# Underwater_Camera_Rev_A.net
KiCad netlist of a schematic drawn in EAGLE
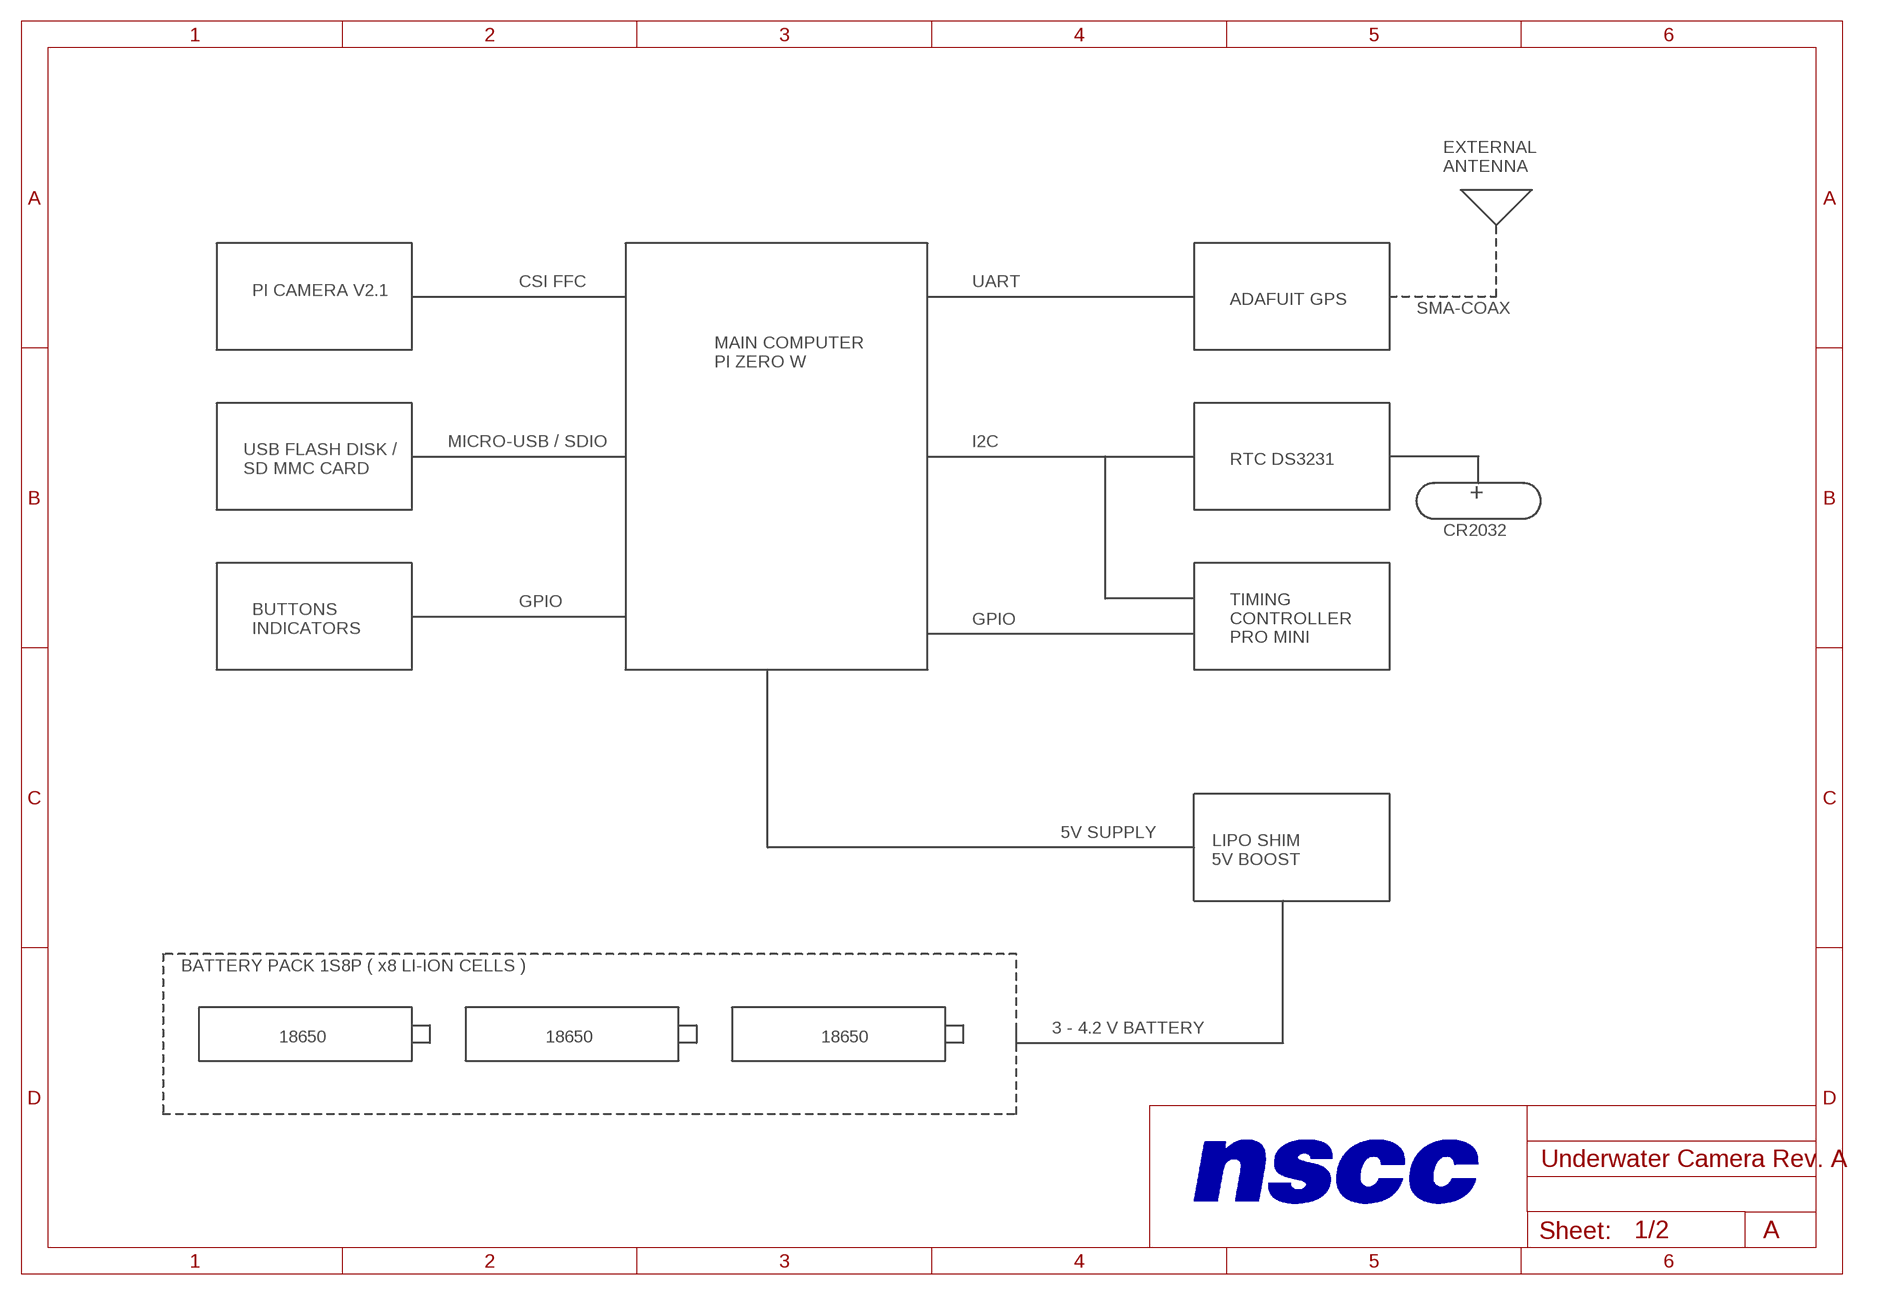
[diagram p0: schematic, sheet 1]
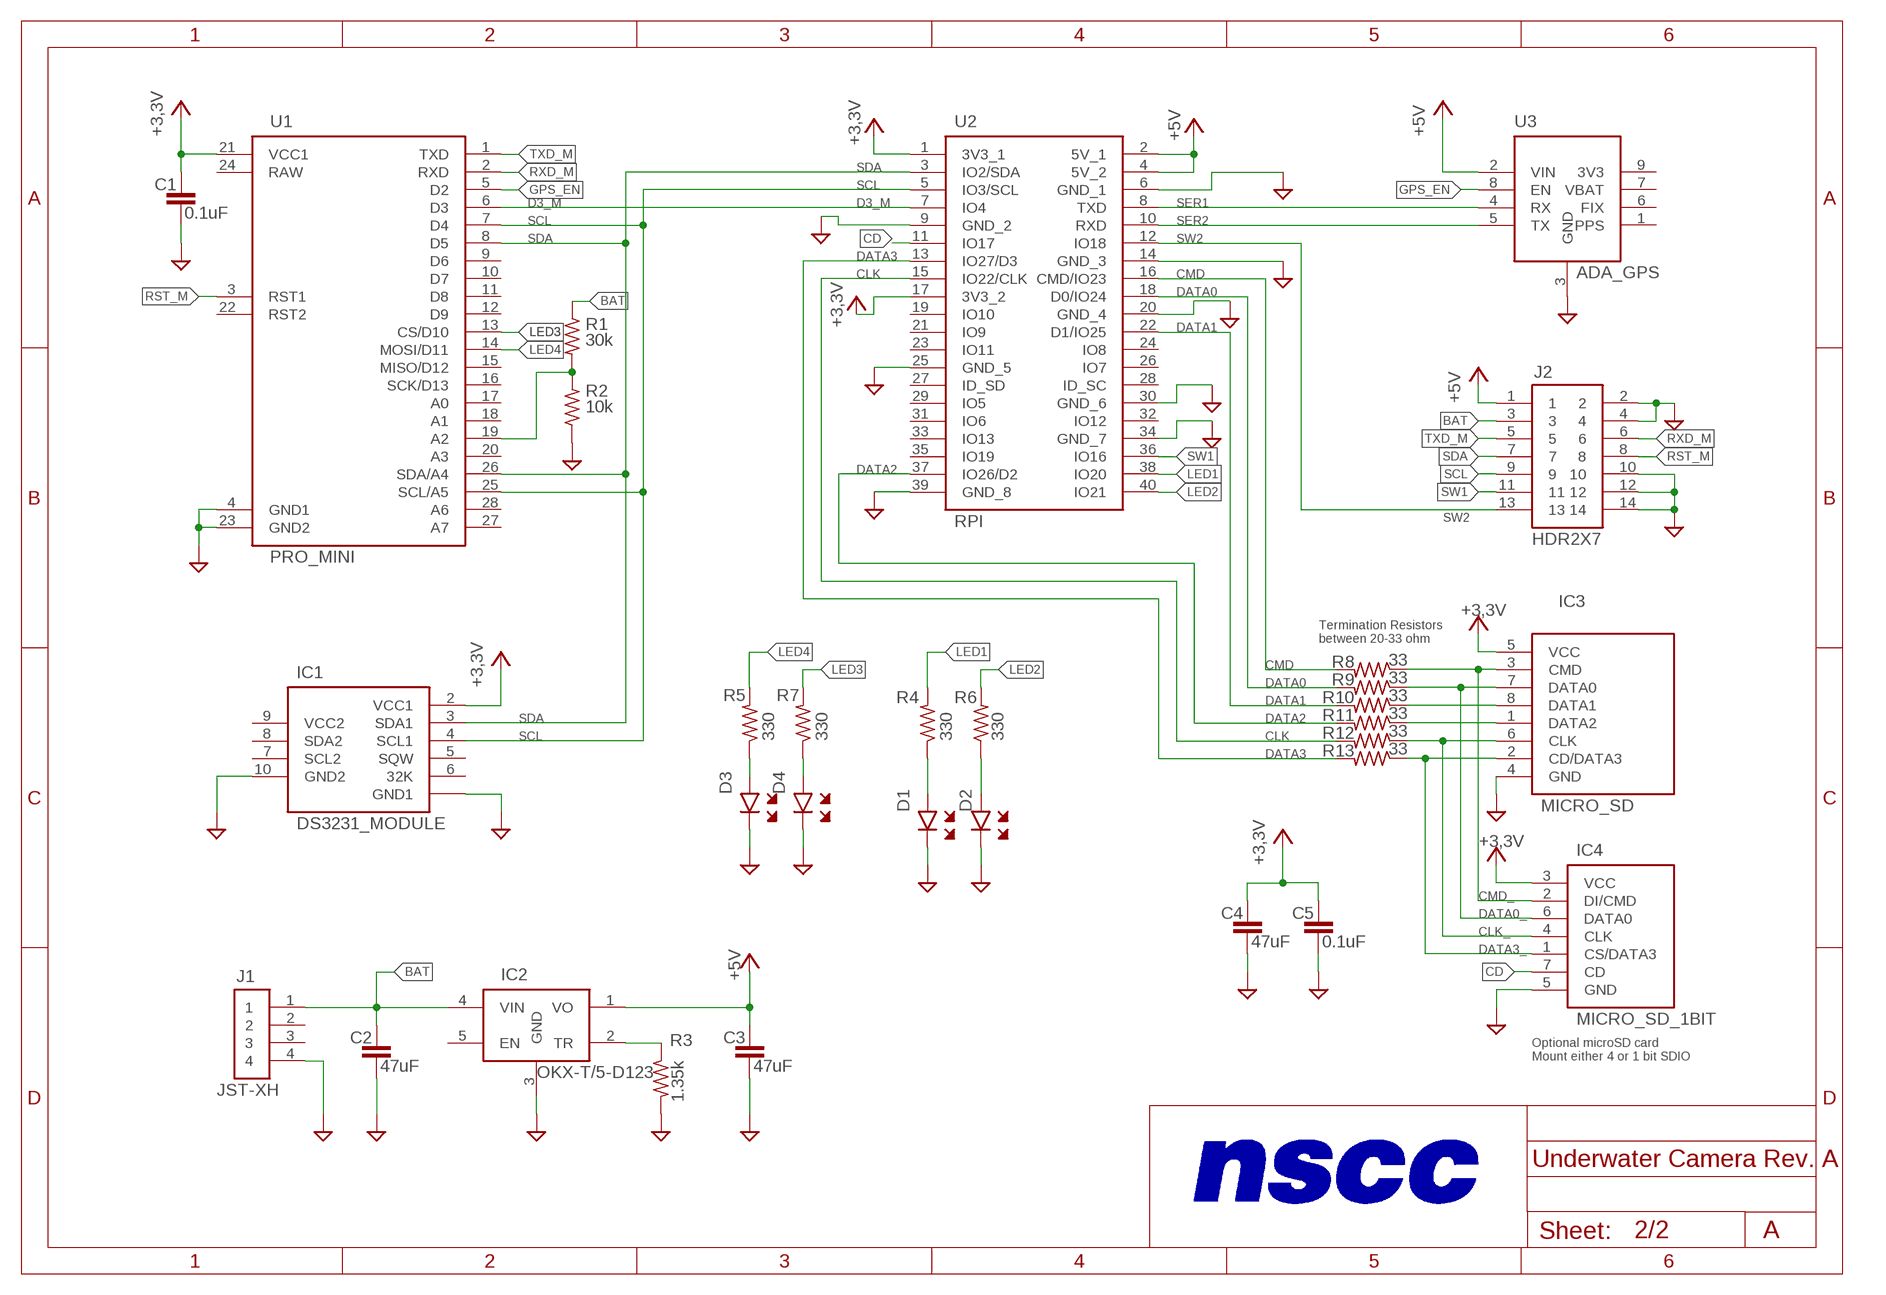
[diagram p1: schematic, sheet 2]

(export (version "E")
  (design (tool "Eeschema 10.0.6"))
  (components
    (comp (ref "C1")
      (value "0.1uF")
      (footprint "eagle-import:CAPPRD254W65D300H300B")
      (libsource (lib "eagle-import") (part "CAP_THCAP-TH-2MM"))
    )
    (comp (ref "C2")
      (value "47uF")
      (footprint "eagle-import:CAPPRD508W65D1000H1100B")
      (libsource (lib "eagle-import") (part "CAP_THCAP-ELECTRO-5.08"))
    )
    (comp (ref "C3")
      (value "47uF")
      (footprint "eagle-import:CAPPRD508W65D1000H1100B")
      (libsource (lib "eagle-import") (part "CAP_THCAP-ELECTRO-5.08"))
    )
    (comp (ref "C4")
      (value "47uF")
      (footprint "eagle-import:CAPPRD508W65D1000H1100B")
      (libsource (lib "eagle-import") (part "CAP_THCAP-ELECTRO-5.08"))
    )
    (comp (ref "C5")
      (value "0.1uF")
      (footprint "eagle-import:CAPPRD254W65D300H300B")
      (libsource (lib "eagle-import") (part "CAP_THCAP-TH-2MM"))
    )
    (comp (ref "D1")
      (value "LED_THLED-2.54")
      (footprint "eagle-import:LEDRD254W60D565H860B")
      (libsource (lib "eagle-import") (part "LED_THLED-2.54"))
    )
    (comp (ref "D2")
      (value "LED_THLED-2.54")
      (footprint "eagle-import:LEDRD254W60D565H860B")
      (libsource (lib "eagle-import") (part "LED_THLED-2.54"))
    )
    (comp (ref "D3")
      (value "LED_THLED-2.54")
      (footprint "eagle-import:LEDRD254W60D565H860B")
      (libsource (lib "eagle-import") (part "LED_THLED-2.54"))
    )
    (comp (ref "D4")
      (value "LED_THLED-2.54")
      (footprint "eagle-import:LEDRD254W60D565H860B")
      (libsource (lib "eagle-import") (part "LED_THLED-2.54"))
    )
    (comp (ref "IC1")
      (value "DS3231_MODULE")
      (footprint "eagle-import:DS3231_MODULE")
      (libsource (lib "eagle-import") (part "DS3231_MODULE"))
    )
    (comp (ref "IC2")
      (value "OKX-T/5-D123")
      (footprint "eagle-import:OKX-T_5-D12")
      (libsource (lib "eagle-import") (part "OKX-T/5-D123DMODEL"))
    )
    (comp (ref "IC3")
      (value "MICRO_SD")
      (footprint "eagle-import:MICRO_SD_SDIO")
      (libsource (lib "eagle-import") (part "MICRO_SD_SNIFFER"))
    )
    (comp (ref "IC4")
      (value "MICRO_SD_1BIT")
      (footprint "eagle-import:MICRO_SD_SDIO1B")
      (libsource (lib "eagle-import") (part "MICRO_SD"))
    )
    (comp (ref "J1")
      (value "JST-XH")
      (footprint "eagle-import:HDR1X4")
      (libsource (lib "eagle-import") (part "HDR1X4JST-XH"))
    )
    (comp (ref "J2")
      (value "HDR2X7")
      (footprint "eagle-import:HDR2X7")
      (libsource (lib "eagle-import") (part "HDR2X7HDR2X7"))
    )
    (comp (ref "R1")
      (value "30k")
      (footprint "eagle-import:RESAD1176W63L850D250B")
      (libsource (lib "eagle-import") (part "RES_THRES-D8.5"))
    )
    (comp (ref "R2")
      (value "10k")
      (footprint "eagle-import:RESAD1176W63L850D250B")
      (libsource (lib "eagle-import") (part "RES_THRES-D8.5"))
    )
    (comp (ref "R3")
      (value "1.35k")
      (footprint "eagle-import:RESAD1176W63L850D250B")
      (libsource (lib "eagle-import") (part "RES_THRES-D8.5"))
    )
    (comp (ref "R4")
      (value "330")
      (footprint "eagle-import:RESAD1176W63L850D250B")
      (libsource (lib "eagle-import") (part "RES_THRES-D8.5"))
    )
    (comp (ref "R5")
      (value "330")
      (footprint "eagle-import:RESAD1176W63L850D250B")
      (libsource (lib "eagle-import") (part "RES_THRES-D8.5"))
    )
    (comp (ref "R6")
      (value "330")
      (footprint "eagle-import:RESAD1176W63L850D250B")
      (libsource (lib "eagle-import") (part "RES_THRES-D8.5"))
    )
    (comp (ref "R7")
      (value "330")
      (footprint "eagle-import:RESAD1176W63L850D250B")
      (libsource (lib "eagle-import") (part "RES_THRES-D8.5"))
    )
    (comp (ref "R8")
      (value "33")
      (footprint "eagle-import:RESAD1176W63L850D250B")
      (libsource (lib "eagle-import") (part "RES_THRES-D8.5"))
    )
    (comp (ref "R9")
      (value "33")
      (footprint "eagle-import:RESAD1176W63L850D250B")
      (libsource (lib "eagle-import") (part "RES_THRES-D8.5"))
    )
    (comp (ref "R10")
      (value "33")
      (footprint "eagle-import:RESAD1176W63L850D250B")
      (libsource (lib "eagle-import") (part "RES_THRES-D8.5"))
    )
    (comp (ref "R11")
      (value "33")
      (footprint "eagle-import:RESAD1176W63L850D250B")
      (libsource (lib "eagle-import") (part "RES_THRES-D8.5"))
    )
    (comp (ref "R12")
      (value "33")
      (footprint "eagle-import:RESAD1176W63L850D250B")
      (libsource (lib "eagle-import") (part "RES_THRES-D8.5"))
    )
    (comp (ref "R13")
      (value "33")
      (footprint "eagle-import:RESAD1176W63L850D250B")
      (libsource (lib "eagle-import") (part "RES_THRES-D8.5"))
    )
    (comp (ref "U1")
      (value "PRO_MINI")
      (footprint "eagle-import:PRO_MINI")
      (libsource (lib "eagle-import") (part "PRO_MINI"))
    )
    (comp (ref "U2")
      (value "RPI")
      (footprint "eagle-import:PI_ZERO_W")
      (libsource (lib "eagle-import") (part "RPI"))
    )
    (comp (ref "U3")
      (value "ADA_GPS")
      (footprint "eagle-import:ADA_ULTIMATE_GPS")
      (libsource (lib "eagle-import") (part "ADA_ULTIMATE_GPS9P_BREAKOUT"))
    )
  )
  (nets
    (net (code "1") (name "+3,3V") (class "Default")
      (node (ref "C1") (pin "1") (pinfunction "1_1") (pintype "passive"))
      (node (ref "C4") (pin "1") (pinfunction "1_1") (pintype "passive"))
      (node (ref "C5") (pin "1") (pinfunction "1_1") (pintype "passive"))
      (node (ref "IC1") (pin "2") (pinfunction "VCC1_2") (pintype "bidirectional"))
      (node (ref "IC3") (pin "5") (pinfunction "VCC_5") (pintype "bidirectional"))
      (node (ref "IC4") (pin "3") (pinfunction "VCC_3") (pintype "bidirectional"))
      (node (ref "U1") (pin "21") (pinfunction "VCC1_21") (pintype "bidirectional"))
      (node (ref "U2") (pin "1") (pinfunction "3V3_1_1") (pintype "bidirectional"))
      (node (ref "U2") (pin "17") (pinfunction "3V3_2_17") (pintype "bidirectional"))
    )
    (net (code "2") (name "+5V") (class "Default")
      (node (ref "C3") (pin "1") (pinfunction "1_1") (pintype "passive"))
      (node (ref "IC2") (pin "1") (pinfunction "VO_1") (pintype "bidirectional"))
      (node (ref "J2") (pin "1") (pinfunction "1_1") (pintype "bidirectional"))
      (node (ref "U2") (pin "2") (pinfunction "5V_1_2") (pintype "bidirectional"))
      (node (ref "U2") (pin "4") (pinfunction "5V_2_4") (pintype "bidirectional"))
      (node (ref "U3") (pin "2") (pinfunction "VIN_2") (pintype "bidirectional"))
    )
    (net (code "3") (name "BAT") (class "Default")
      (node (ref "C2") (pin "1") (pinfunction "1_1") (pintype "passive"))
      (node (ref "IC2") (pin "4") (pinfunction "VIN_4") (pintype "bidirectional"))
      (node (ref "J1") (pin "1") (pinfunction "1_1") (pintype "bidirectional"))
      (node (ref "J2") (pin "3") (pinfunction "3_3") (pintype "bidirectional"))
      (node (ref "R1") (pin "1") (pinfunction "1_1") (pintype "passive"))
    )
    (net (code "4") (name "CD") (class "Default")
      (node (ref "IC4") (pin "7") (pinfunction "CD_7") (pintype "bidirectional"))
      (node (ref "U2") (pin "11") (pinfunction "IO17_11") (pintype "bidirectional"))
    )
    (net (code "5") (name "CLK") (class "Default")
      (node (ref "R12") (pin "2") (pinfunction "2_2") (pintype "passive"))
      (node (ref "U2") (pin "15") (pinfunction "IO22/CLK_15") (pintype "bidirectional"))
    )
    (net (code "6") (name "CLK_") (class "Default")
      (node (ref "IC3") (pin "6") (pinfunction "CLK_6") (pintype "bidirectional"))
      (node (ref "IC4") (pin "4") (pinfunction "CLK_4") (pintype "bidirectional"))
      (node (ref "R12") (pin "1") (pinfunction "1_1") (pintype "passive"))
    )
    (net (code "7") (name "CMD") (class "Default")
      (node (ref "R8") (pin "2") (pinfunction "2_2") (pintype "passive"))
      (node (ref "U2") (pin "16") (pinfunction "CMD/IO23_16") (pintype "bidirectional"))
    )
    (net (code "8") (name "CMD_") (class "Default")
      (node (ref "IC3") (pin "3") (pinfunction "CMD_3") (pintype "bidirectional"))
      (node (ref "IC4") (pin "2") (pinfunction "DI/CMD_2") (pintype "bidirectional"))
      (node (ref "R8") (pin "1") (pinfunction "1_1") (pintype "passive"))
    )
    (net (code "9") (name "D3_M") (class "Default")
      (node (ref "U1") (pin "6") (pinfunction "D3_6") (pintype "bidirectional"))
      (node (ref "U2") (pin "7") (pinfunction "IO4_7") (pintype "bidirectional"))
    )
    (net (code "10") (name "DATA0") (class "Default")
      (node (ref "R9") (pin "2") (pinfunction "2_2") (pintype "passive"))
      (node (ref "U2") (pin "18") (pinfunction "D0/IO24_18") (pintype "bidirectional"))
    )
    (net (code "11") (name "DATA0_") (class "Default")
      (node (ref "IC3") (pin "7") (pinfunction "DATA0_7") (pintype "bidirectional"))
      (node (ref "IC4") (pin "6") (pinfunction "DATA0_6") (pintype "bidirectional"))
      (node (ref "R9") (pin "1") (pinfunction "1_1") (pintype "passive"))
    )
    (net (code "12") (name "DATA1") (class "Default")
      (node (ref "R10") (pin "2") (pinfunction "2_2") (pintype "passive"))
      (node (ref "U2") (pin "22") (pinfunction "D1/IO25_22") (pintype "bidirectional"))
    )
    (net (code "13") (name "DATA2") (class "Default")
      (node (ref "R11") (pin "2") (pinfunction "2_2") (pintype "passive"))
      (node (ref "U2") (pin "37") (pinfunction "IO26/D2_37") (pintype "bidirectional"))
    )
    (net (code "14") (name "DATA3") (class "Default")
      (node (ref "R13") (pin "2") (pinfunction "2_2") (pintype "passive"))
      (node (ref "U2") (pin "13") (pinfunction "IO27/D3_13") (pintype "bidirectional"))
    )
    (net (code "15") (name "DATA3_") (class "Default")
      (node (ref "IC3") (pin "2") (pinfunction "CD/DATA3_2") (pintype "bidirectional"))
      (node (ref "IC4") (pin "1") (pinfunction "CS/DATA3_1") (pintype "bidirectional"))
      (node (ref "R13") (pin "1") (pinfunction "1_1") (pintype "passive"))
    )
    (net (code "16") (name "GND") (class "Default")
      (node (ref "C1") (pin "2") (pinfunction "2_2") (pintype "passive"))
      (node (ref "C2") (pin "2") (pinfunction "2_2") (pintype "passive"))
      (node (ref "C3") (pin "2") (pinfunction "2_2") (pintype "passive"))
      (node (ref "C4") (pin "2") (pinfunction "2_2") (pintype "passive"))
      (node (ref "C5") (pin "2") (pinfunction "2_2") (pintype "passive"))
      (node (ref "D1") (pin "2") (pinfunction "P$2_2") (pintype "bidirectional"))
      (node (ref "D2") (pin "2") (pinfunction "P$2_2") (pintype "bidirectional"))
      (node (ref "D3") (pin "2") (pinfunction "P$2_2") (pintype "bidirectional"))
      (node (ref "D4") (pin "2") (pinfunction "P$2_2") (pintype "bidirectional"))
      (node (ref "IC1") (pin "1") (pinfunction "GND1_1") (pintype "bidirectional"))
      (node (ref "IC1") (pin "10") (pinfunction "GND2_10") (pintype "bidirectional"))
      (node (ref "IC2") (pin "3") (pinfunction "GND_3") (pintype "bidirectional"))
      (node (ref "IC3") (pin "4") (pinfunction "GND_4") (pintype "bidirectional"))
      (node (ref "IC4") (pin "5") (pinfunction "GND_5") (pintype "bidirectional"))
      (node (ref "J1") (pin "4") (pinfunction "4_4") (pintype "bidirectional"))
      (node (ref "J2") (pin "10") (pinfunction "10_10") (pintype "bidirectional"))
      (node (ref "J2") (pin "12") (pinfunction "12_12") (pintype "bidirectional"))
      (node (ref "J2") (pin "14") (pinfunction "14_14") (pintype "bidirectional"))
      (node (ref "J2") (pin "2") (pinfunction "2_2") (pintype "bidirectional"))
      (node (ref "J2") (pin "4") (pinfunction "4_4") (pintype "bidirectional"))
      (node (ref "R2") (pin "1") (pinfunction "1_1") (pintype "passive"))
      (node (ref "R3") (pin "2") (pinfunction "2_2") (pintype "passive"))
      (node (ref "U1") (pin "23") (pinfunction "GND2_23") (pintype "bidirectional"))
      (node (ref "U1") (pin "4") (pinfunction "GND1_4") (pintype "bidirectional"))
      (node (ref "U2") (pin "14") (pinfunction "GND_3_14") (pintype "bidirectional"))
      (node (ref "U2") (pin "20") (pinfunction "GND_4_20") (pintype "bidirectional"))
      (node (ref "U2") (pin "25") (pinfunction "GND_5_25") (pintype "bidirectional"))
      (node (ref "U2") (pin "30") (pinfunction "GND_6_30") (pintype "bidirectional"))
      (node (ref "U2") (pin "34") (pinfunction "GND_7_34") (pintype "bidirectional"))
      (node (ref "U2") (pin "39") (pinfunction "GND_8_39") (pintype "bidirectional"))
      (node (ref "U2") (pin "6") (pinfunction "GND_1_6") (pintype "bidirectional"))
      (node (ref "U2") (pin "9") (pinfunction "GND_2_9") (pintype "bidirectional"))
      (node (ref "U3") (pin "3") (pinfunction "GND_3") (pintype "bidirectional"))
    )
    (net (code "17") (name "GPS_EN") (class "Default")
      (node (ref "U1") (pin "5") (pinfunction "D2_5") (pintype "bidirectional"))
      (node (ref "U3") (pin "8") (pinfunction "EN_8") (pintype "bidirectional"))
    )
    (net (code "18") (name "LED1") (class "Default")
      (node (ref "R4") (pin "2") (pinfunction "2_2") (pintype "passive"))
      (node (ref "U2") (pin "38") (pinfunction "IO20_38") (pintype "bidirectional"))
    )
    (net (code "19") (name "LED2") (class "Default")
      (node (ref "R6") (pin "2") (pinfunction "2_2") (pintype "passive"))
      (node (ref "U2") (pin "40") (pinfunction "IO21_40") (pintype "bidirectional"))
    )
    (net (code "20") (name "LED3") (class "Default")
      (node (ref "R7") (pin "2") (pinfunction "2_2") (pintype "passive"))
      (node (ref "U1") (pin "13") (pinfunction "CS/D10_13") (pintype "bidirectional"))
    )
    (net (code "21") (name "LED4") (class "Default")
      (node (ref "R5") (pin "2") (pinfunction "2_2") (pintype "passive"))
      (node (ref "U1") (pin "14") (pinfunction "MOSI/D11_14") (pintype "bidirectional"))
    )
    (net (code "22") (name "Net-(D1-P$1)") (class "Default")
      (node (ref "D1") (pin "1") (pinfunction "P$1_1") (pintype "bidirectional"))
      (node (ref "R4") (pin "1") (pinfunction "1_1") (pintype "passive"))
    )
    (net (code "23") (name "Net-(D2-P$1)") (class "Default")
      (node (ref "D2") (pin "1") (pinfunction "P$1_1") (pintype "bidirectional"))
      (node (ref "R6") (pin "1") (pinfunction "1_1") (pintype "passive"))
    )
    (net (code "24") (name "Net-(D3-P$1)") (class "Default")
      (node (ref "D3") (pin "1") (pinfunction "P$1_1") (pintype "bidirectional"))
      (node (ref "R5") (pin "1") (pinfunction "1_1") (pintype "passive"))
    )
    (net (code "25") (name "Net-(D4-P$1)") (class "Default")
      (node (ref "D4") (pin "1") (pinfunction "P$1_1") (pintype "bidirectional"))
      (node (ref "R7") (pin "1") (pinfunction "1_1") (pintype "passive"))
    )
    (net (code "26") (name "Net-(IC2-TR)") (class "Default")
      (node (ref "IC2") (pin "2") (pinfunction "TR_2") (pintype "bidirectional"))
      (node (ref "R3") (pin "1") (pinfunction "1_1") (pintype "passive"))
    )
    (net (code "27") (name "Net-(IC3-DATA1)") (class "Default")
      (node (ref "IC3") (pin "8") (pinfunction "DATA1_8") (pintype "bidirectional"))
      (node (ref "R10") (pin "1") (pinfunction "1_1") (pintype "passive"))
    )
    (net (code "28") (name "Net-(IC3-DATA2)") (class "Default")
      (node (ref "IC3") (pin "1") (pinfunction "DATA2_1") (pintype "bidirectional"))
      (node (ref "R11") (pin "1") (pinfunction "1_1") (pintype "passive"))
    )
    (net (code "29") (name "Net-(U1-A2)") (class "Default")
      (node (ref "R1") (pin "2") (pinfunction "2_2") (pintype "passive"))
      (node (ref "R2") (pin "2") (pinfunction "2_2") (pintype "passive"))
      (node (ref "U1") (pin "19") (pinfunction "A2_19") (pintype "bidirectional"))
    )
    (net (code "30") (name "RST_M") (class "Default")
      (node (ref "J2") (pin "8") (pinfunction "8_8") (pintype "bidirectional"))
      (node (ref "U1") (pin "3") (pinfunction "RST1_3") (pintype "bidirectional"))
    )
    (net (code "31") (name "RXD_M") (class "Default")
      (node (ref "J2") (pin "6") (pinfunction "6_6") (pintype "bidirectional"))
      (node (ref "U1") (pin "2") (pinfunction "RXD_2") (pintype "bidirectional"))
    )
    (net (code "32") (name "SCL") (class "Default")
      (node (ref "IC1") (pin "4") (pinfunction "SCL1_4") (pintype "bidirectional"))
      (node (ref "J2") (pin "9") (pinfunction "9_9") (pintype "bidirectional"))
      (node (ref "U1") (pin "25") (pinfunction "SCL/A5_25") (pintype "bidirectional"))
      (node (ref "U1") (pin "7") (pinfunction "D4_7") (pintype "bidirectional"))
      (node (ref "U2") (pin "5") (pinfunction "IO3/SCL_5") (pintype "bidirectional"))
    )
    (net (code "33") (name "SDA") (class "Default")
      (node (ref "IC1") (pin "3") (pinfunction "SDA1_3") (pintype "bidirectional"))
      (node (ref "J2") (pin "7") (pinfunction "7_7") (pintype "bidirectional"))
      (node (ref "U1") (pin "26") (pinfunction "SDA/A4_26") (pintype "bidirectional"))
      (node (ref "U1") (pin "8") (pinfunction "D5_8") (pintype "bidirectional"))
      (node (ref "U2") (pin "3") (pinfunction "IO2/SDA_3") (pintype "bidirectional"))
    )
    (net (code "34") (name "SER1") (class "Default")
      (node (ref "U2") (pin "8") (pinfunction "TXD_8") (pintype "bidirectional"))
      (node (ref "U3") (pin "4") (pinfunction "RX_4") (pintype "bidirectional"))
    )
    (net (code "35") (name "SER2") (class "Default")
      (node (ref "U2") (pin "10") (pinfunction "RXD_10") (pintype "bidirectional"))
      (node (ref "U3") (pin "5") (pinfunction "TX_5") (pintype "bidirectional"))
    )
    (net (code "36") (name "SW1") (class "Default")
      (node (ref "J2") (pin "11") (pinfunction "11_11") (pintype "bidirectional"))
      (node (ref "U2") (pin "36") (pinfunction "IO16_36") (pintype "bidirectional"))
    )
    (net (code "37") (name "SW2") (class "Default")
      (node (ref "J2") (pin "13") (pinfunction "13_13") (pintype "bidirectional"))
      (node (ref "U2") (pin "12") (pinfunction "IO18_12") (pintype "bidirectional"))
    )
    (net (code "38") (name "TXD_M") (class "Default")
      (node (ref "J2") (pin "5") (pinfunction "5_5") (pintype "bidirectional"))
      (node (ref "U1") (pin "1") (pinfunction "TXD_1") (pintype "bidirectional"))
    )
    (net (code "39") (name "unconnected-(IC1-32K-Pad6)") (class "Default")
      (node (ref "IC1") (pin "6") (pinfunction "32K_6") (pintype "bidirectional"))
    )
    (net (code "40") (name "unconnected-(IC1-SCL2-Pad7)") (class "Default")
      (node (ref "IC1") (pin "7") (pinfunction "SCL2_7") (pintype "bidirectional"))
    )
    (net (code "41") (name "unconnected-(IC1-SDA2-Pad8)") (class "Default")
      (node (ref "IC1") (pin "8") (pinfunction "SDA2_8") (pintype "bidirectional"))
    )
    (net (code "42") (name "unconnected-(IC1-SQW-Pad5)") (class "Default")
      (node (ref "IC1") (pin "5") (pinfunction "SQW_5") (pintype "bidirectional"))
    )
    (net (code "43") (name "unconnected-(IC1-VCC2-Pad9)") (class "Default")
      (node (ref "IC1") (pin "9") (pinfunction "VCC2_9") (pintype "bidirectional"))
    )
    (net (code "44") (name "unconnected-(IC2-EN-Pad5)") (class "Default")
      (node (ref "IC2") (pin "5") (pinfunction "EN_5") (pintype "bidirectional"))
    )
    (net (code "45") (name "unconnected-(J1-Pad2)") (class "Default")
      (node (ref "J1") (pin "2") (pinfunction "2_2") (pintype "bidirectional"))
    )
    (net (code "46") (name "unconnected-(J1-Pad3)") (class "Default")
      (node (ref "J1") (pin "3") (pinfunction "3_3") (pintype "bidirectional"))
    )
    (net (code "47") (name "unconnected-(U1-A0-Pad17)") (class "Default")
      (node (ref "U1") (pin "17") (pinfunction "A0_17") (pintype "bidirectional"))
    )
    (net (code "48") (name "unconnected-(U1-A1-Pad18)") (class "Default")
      (node (ref "U1") (pin "18") (pinfunction "A1_18") (pintype "bidirectional"))
    )
    (net (code "49") (name "unconnected-(U1-A3-Pad20)") (class "Default")
      (node (ref "U1") (pin "20") (pinfunction "A3_20") (pintype "bidirectional"))
    )
    (net (code "50") (name "unconnected-(U1-A6-Pad28)") (class "Default")
      (node (ref "U1") (pin "28") (pinfunction "A6_28") (pintype "bidirectional"))
    )
    (net (code "51") (name "unconnected-(U1-A7-Pad27)") (class "Default")
      (node (ref "U1") (pin "27") (pinfunction "A7_27") (pintype "bidirectional"))
    )
    (net (code "52") (name "unconnected-(U1-D6-Pad9)") (class "Default")
      (node (ref "U1") (pin "9") (pinfunction "D6_9") (pintype "bidirectional"))
    )
    (net (code "53") (name "unconnected-(U1-D7-Pad10)") (class "Default")
      (node (ref "U1") (pin "10") (pinfunction "D7_10") (pintype "bidirectional"))
    )
    (net (code "54") (name "unconnected-(U1-D8-Pad11)") (class "Default")
      (node (ref "U1") (pin "11") (pinfunction "D8_11") (pintype "bidirectional"))
    )
    (net (code "55") (name "unconnected-(U1-D9-Pad12)") (class "Default")
      (node (ref "U1") (pin "12") (pinfunction "D9_12") (pintype "bidirectional"))
    )
    (net (code "56") (name "unconnected-(U1-MISO{slash}D12-Pad15)") (class "Default")
      (node (ref "U1") (pin "15") (pinfunction "MISO/D12_15") (pintype "bidirectional"))
    )
    (net (code "57") (name "unconnected-(U1-RAW-Pad24)") (class "Default")
      (node (ref "U1") (pin "24") (pinfunction "RAW_24") (pintype "bidirectional"))
    )
    (net (code "58") (name "unconnected-(U1-RST2-Pad22)") (class "Default")
      (node (ref "U1") (pin "22") (pinfunction "RST2_22") (pintype "bidirectional"))
    )
    (net (code "59") (name "unconnected-(U1-SCK{slash}D13-Pad16)") (class "Default")
      (node (ref "U1") (pin "16") (pinfunction "SCK/D13_16") (pintype "bidirectional"))
    )
    (net (code "60") (name "unconnected-(U2-ID_SC-Pad28)") (class "Default")
      (node (ref "U2") (pin "28") (pinfunction "ID_SC_28") (pintype "bidirectional"))
    )
    (net (code "61") (name "unconnected-(U2-ID_SD-Pad27)") (class "Default")
      (node (ref "U2") (pin "27") (pinfunction "ID_SD_27") (pintype "bidirectional"))
    )
    (net (code "62") (name "unconnected-(U2-IO5-Pad29)") (class "Default")
      (node (ref "U2") (pin "29") (pinfunction "IO5_29") (pintype "bidirectional"))
    )
    (net (code "63") (name "unconnected-(U2-IO6-Pad31)") (class "Default")
      (node (ref "U2") (pin "31") (pinfunction "IO6_31") (pintype "bidirectional"))
    )
    (net (code "64") (name "unconnected-(U2-IO7-Pad26)") (class "Default")
      (node (ref "U2") (pin "26") (pinfunction "IO7_26") (pintype "bidirectional"))
    )
    (net (code "65") (name "unconnected-(U2-IO8-Pad24)") (class "Default")
      (node (ref "U2") (pin "24") (pinfunction "IO8_24") (pintype "bidirectional"))
    )
    (net (code "66") (name "unconnected-(U2-IO9-Pad21)") (class "Default")
      (node (ref "U2") (pin "21") (pinfunction "IO9_21") (pintype "bidirectional"))
    )
    (net (code "67") (name "unconnected-(U2-IO10-Pad19)") (class "Default")
      (node (ref "U2") (pin "19") (pinfunction "IO10_19") (pintype "bidirectional"))
    )
    (net (code "68") (name "unconnected-(U2-IO11-Pad23)") (class "Default")
      (node (ref "U2") (pin "23") (pinfunction "IO11_23") (pintype "bidirectional"))
    )
    (net (code "69") (name "unconnected-(U2-IO12-Pad32)") (class "Default")
      (node (ref "U2") (pin "32") (pinfunction "IO12_32") (pintype "bidirectional"))
    )
    (net (code "70") (name "unconnected-(U2-IO13-Pad33)") (class "Default")
      (node (ref "U2") (pin "33") (pinfunction "IO13_33") (pintype "bidirectional"))
    )
    (net (code "71") (name "unconnected-(U2-IO19-Pad35)") (class "Default")
      (node (ref "U2") (pin "35") (pinfunction "IO19_35") (pintype "bidirectional"))
    )
    (net (code "72") (name "unconnected-(U3-3V3-Pad9)") (class "Default")
      (node (ref "U3") (pin "9") (pinfunction "3V3_9") (pintype "bidirectional"))
    )
    (net (code "73") (name "unconnected-(U3-FIX-Pad6)") (class "Default")
      (node (ref "U3") (pin "6") (pinfunction "FIX_6") (pintype "bidirectional"))
    )
    (net (code "74") (name "unconnected-(U3-PPS-Pad1)") (class "Default")
      (node (ref "U3") (pin "1") (pinfunction "PPS_1") (pintype "bidirectional"))
    )
    (net (code "75") (name "unconnected-(U3-VBAT-Pad7)") (class "Default")
      (node (ref "U3") (pin "7") (pinfunction "VBAT_7") (pintype "bidirectional"))
    )
  )
)
